# tmkibot1_2_1_MAX7219_8_8_Dot_Matrix.net
KiCad netlist of a schematic drawn in EasyEDA Pro
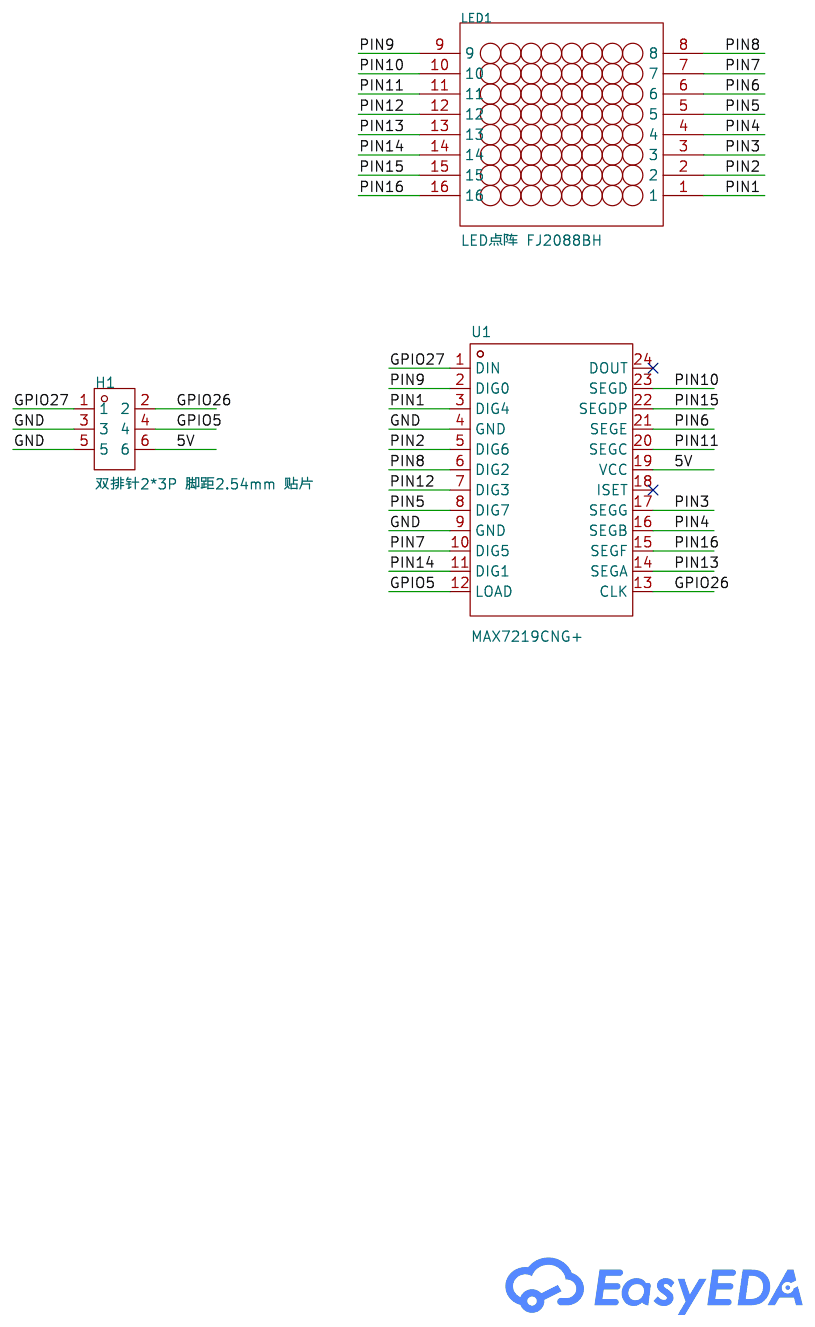
[diagram p0: schematic sheet]

(export (version "E")
  (design (tool "Eeschema 10.0.6"))
  (components
    (comp (ref "H1")
      (value "双排针2*3P 脚距2.54mm 贴片")
      (footprint "easyedapro:HDR-SMD_6P-P2.54-V-M-R2-C3-S2.54-LS7.4")
      (fields (field (name "Manufacturer") "BOOMELE(博穆精密)"))
      (libsource (lib "easyedapro") (part "双排针2*3P  脚距2.54MM  贴片"))
    )
    (comp (ref "LED1")
      (value "LED点阵 FJ2088BH")
      (footprint "easyedapro:LED-ARRAY-TH_L61.0-W61.0-P2.54-LS45.7-L")
      (description "Dot Matrix Number:8x8 Emitting Color:Red Polarity:共阴极")
      (fields (field (name "Manufacturer") "志浩"))
      (libsource (lib "easyedapro") (part "LED FJ2088BH"))
    )
    (comp (ref "U1")
      (value "MAX7219CNG+")
      (footprint "easyedapro:DIP-24_L31.7-W6.6-P2.54-LS7.6-BL-2")
      (fields (field (name "Manufacturer") "ADI(亚德诺)/MAXIM(美信)"))
      (libsource (lib "easyedapro") (part "max7219cng"))
    )
  )
  (nets
    (net (code "1") (name "/5V") (class "Default")
      (node (ref "H1") (pin "6") (pinfunction "6_6") (pintype "input"))
      (node (ref "U1") (pin "19") (pinfunction "VCC_19") (pintype "unspecified"))
    )
    (net (code "2") (name "/GND") (class "Default")
      (node (ref "H1") (pin "3") (pinfunction "3_3") (pintype "input"))
      (node (ref "H1") (pin "5") (pinfunction "5_5") (pintype "input"))
      (node (ref "U1") (pin "4") (pinfunction "GND_4") (pintype "unspecified"))
      (node (ref "U1") (pin "9") (pinfunction "GND_9") (pintype "unspecified"))
    )
    (net (code "3") (name "/GPIO5") (class "Default")
      (node (ref "H1") (pin "4") (pinfunction "4_4") (pintype "input"))
      (node (ref "U1") (pin "12") (pinfunction "LOAD_12") (pintype "unspecified"))
    )
    (net (code "4") (name "/GPIO26") (class "Default")
      (node (ref "H1") (pin "2") (pinfunction "2_2") (pintype "input"))
      (node (ref "U1") (pin "13") (pinfunction "CLK_13") (pintype "unspecified"))
    )
    (net (code "5") (name "/GPIO27") (class "Default")
      (node (ref "H1") (pin "1") (pinfunction "1_1") (pintype "input"))
      (node (ref "U1") (pin "1") (pinfunction "DIN_1") (pintype "unspecified"))
    )
    (net (code "6") (name "/PIN1") (class "Default")
      (node (ref "LED1") (pin "1") (pinfunction "1_1") (pintype "input"))
      (node (ref "U1") (pin "3") (pinfunction "DIG4_3") (pintype "unspecified"))
    )
    (net (code "7") (name "/PIN2") (class "Default")
      (node (ref "LED1") (pin "2") (pinfunction "2_2") (pintype "input"))
      (node (ref "U1") (pin "5") (pinfunction "DIG6_5") (pintype "unspecified"))
    )
    (net (code "8") (name "/PIN3") (class "Default")
      (node (ref "LED1") (pin "3") (pinfunction "3_3") (pintype "input"))
      (node (ref "U1") (pin "17") (pinfunction "SEGG_17") (pintype "unspecified"))
    )
    (net (code "9") (name "/PIN4") (class "Default")
      (node (ref "LED1") (pin "4") (pinfunction "4_4") (pintype "input"))
      (node (ref "U1") (pin "16") (pinfunction "SEGB_16") (pintype "unspecified"))
    )
    (net (code "10") (name "/PIN5") (class "Default")
      (node (ref "LED1") (pin "5") (pinfunction "5_5") (pintype "input"))
      (node (ref "U1") (pin "8") (pinfunction "DIG7_8") (pintype "unspecified"))
    )
    (net (code "11") (name "/PIN6") (class "Default")
      (node (ref "LED1") (pin "6") (pinfunction "6_6") (pintype "input"))
      (node (ref "U1") (pin "21") (pinfunction "SEGE_21") (pintype "unspecified"))
    )
    (net (code "12") (name "/PIN7") (class "Default")
      (node (ref "LED1") (pin "7") (pinfunction "7_7") (pintype "input"))
      (node (ref "U1") (pin "10") (pinfunction "DIG5_10") (pintype "unspecified"))
    )
    (net (code "13") (name "/PIN8") (class "Default")
      (node (ref "LED1") (pin "8") (pinfunction "8_8") (pintype "input"))
      (node (ref "U1") (pin "6") (pinfunction "DIG2_6") (pintype "unspecified"))
    )
    (net (code "14") (name "/PIN9") (class "Default")
      (node (ref "LED1") (pin "9") (pinfunction "9_9") (pintype "input"))
      (node (ref "U1") (pin "2") (pinfunction "DIG0_2") (pintype "unspecified"))
    )
    (net (code "15") (name "/PIN10") (class "Default")
      (node (ref "LED1") (pin "10") (pinfunction "10_10") (pintype "input"))
      (node (ref "U1") (pin "23") (pinfunction "SEGD_23") (pintype "unspecified"))
    )
    (net (code "16") (name "/PIN11") (class "Default")
      (node (ref "LED1") (pin "11") (pinfunction "11_11") (pintype "input"))
      (node (ref "U1") (pin "20") (pinfunction "SEGC_20") (pintype "unspecified"))
    )
    (net (code "17") (name "/PIN12") (class "Default")
      (node (ref "LED1") (pin "12") (pinfunction "12_12") (pintype "input"))
      (node (ref "U1") (pin "7") (pinfunction "DIG3_7") (pintype "unspecified"))
    )
    (net (code "18") (name "/PIN13") (class "Default")
      (node (ref "LED1") (pin "13") (pinfunction "13_13") (pintype "input"))
      (node (ref "U1") (pin "14") (pinfunction "SEGA_14") (pintype "unspecified"))
    )
    (net (code "19") (name "/PIN14") (class "Default")
      (node (ref "LED1") (pin "14") (pinfunction "14_14") (pintype "input"))
      (node (ref "U1") (pin "11") (pinfunction "DIG1_11") (pintype "unspecified"))
    )
    (net (code "20") (name "/PIN15") (class "Default")
      (node (ref "LED1") (pin "15") (pinfunction "15_15") (pintype "input"))
      (node (ref "U1") (pin "22") (pinfunction "SEGDP_22") (pintype "unspecified"))
    )
    (net (code "21") (name "/PIN16") (class "Default")
      (node (ref "LED1") (pin "16") (pinfunction "16_16") (pintype "input"))
      (node (ref "U1") (pin "15") (pinfunction "SEGF_15") (pintype "unspecified"))
    )
    (net (code "22") (name "unconnected-(U1-DOUT-Pad24)") (class "Default")
      (node (ref "U1") (pin "24") (pinfunction "DOUT_24") (pintype "unspecified+no_connect"))
    )
    (net (code "23") (name "unconnected-(U1-ISET-Pad18)") (class "Default")
      (node (ref "U1") (pin "18") (pinfunction "ISET_18") (pintype "unspecified+no_connect"))
    )
  )
)
